# rs485.net
KiCad netlist of a schematic drawn in Altium Designer
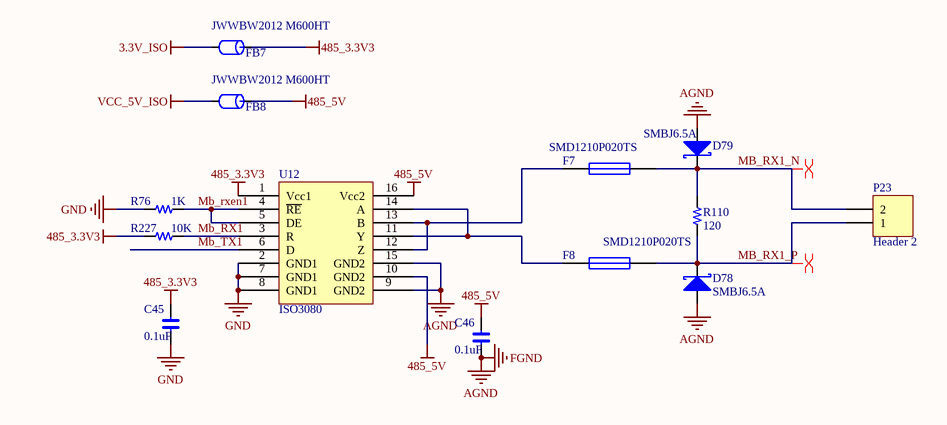
[diagram p0: rs485.SchDoc]

(export (version "E")
  (design (tool "Eeschema 10.0.6"))
  (components
    (comp (ref "C45")
      (value "0.1uF")
      (footprint "0603C")
      (description "C")
      (libsource (lib "Schlib_20110825") (part "C"))
    )
    (comp (ref "C46")
      (value "0.1uF")
      (footprint "0603C")
      (description "C")
      (libsource (lib "Schlib_20110825") (part "C"))
    )
    (comp (ref "D78")
      (value "SMBJ6.5A")
      (footprint "SMB")
      (description "Schottky Diode")
      (libsource (lib "*") (part "DIODE S"))
    )
    (comp (ref "D79")
      (value "SMBJ6.5A")
      (footprint "SMB")
      (description "Schottky Diode")
      (libsource (lib "*") (part "DIODE S"))
    )
    (comp (ref "F7")
      (value "SMD1210P020TS")
      (footprint "1206R")
      (description "Fuse")
      (fields (field (name "PUBLISHER") "Altium Limited"))
      (libsource (lib "Miscellaneous Devices") (part "Fuse 1"))
    )
    (comp (ref "F8")
      (value "SMD1210P020TS")
      (footprint "1206R")
      (description "Fuse")
      (fields (field (name "PUBLISHER") "Altium Limited"))
      (libsource (lib "Miscellaneous Devices") (part "Fuse 1"))
    )
    (comp (ref "FB7")
      (value "JWWBW2012 M600HT")
      (footprint "0805CZ")
      (libsource (lib "Schlib_20110825") (part "FB"))
    )
    (comp (ref "FB8")
      (value "JWWBW2012 M600HT")
      (footprint "0805CZ")
      (libsource (lib "Schlib_20110825") (part "FB"))
    )
    (comp (ref "P23")
      (value "Header 2")
      (footprint "2X2.54MMZ")
      (description "Header, 2-Pin")
      (fields (field (name "PUBLISHER") "Altium Limited"))
      (libsource (lib "Miscellaneous Connectors") (part "Header 2"))
    )
    (comp (ref "R76") (value "1K") (footprint "0603R") (description "R") (libsource (lib "JRJ_1") (part "R")))
    (comp (ref "R110")
      (value "120")
      (footprint "0603R")
      (description "R")
      (libsource (lib "JRJ_1") (part "R"))
    )
    (comp (ref "R227")
      (value "10K")
      (footprint "0603R")
      (description "R")
      (libsource (lib "JRJ_1") (part "R"))
    )
    (comp (ref "U12") (value "ISO3080") (footprint "SO-16") (libsource (lib "Schlib1") (part "ISO3080")))
  )
  (nets
    (net (code "1") (name "/MB_RX1_N") (class "Default")
      (node (ref "D79") (pin "2") (pinfunction "K_2") (pintype "passive"))
      (node (ref "F7") (pin "2") (pinfunction "2_2") (pintype "passive"))
      (node (ref "P23") (pin "2") (pinfunction "2_2") (pintype "passive"))
      (node (ref "R110") (pin "1") (pintype "passive"))
    )
    (net (code "2") (name "/MB_RX1_P") (class "Default")
      (node (ref "D78") (pin "2") (pinfunction "K_2") (pintype "passive"))
      (node (ref "F8") (pin "2") (pinfunction "2_2") (pintype "passive"))
      (node (ref "P23") (pin "1") (pinfunction "1_1") (pintype "passive"))
      (node (ref "R110") (pin "2") (pintype "passive"))
    )
    (net (code "3") (name "/Mb_RX1") (class "Default")
      (node (ref "R227") (pin "1") (pintype "passive"))
      (node (ref "U12") (pin "3") (pinfunction "R_3") (pintype "passive"))
    )
    (net (code "4") (name "/Mb_TX1") (class "Default")
      (node (ref "U12") (pin "6") (pinfunction "D_6") (pintype "passive"))
    )
    (net (code "5") (name "/Mb_rxen1") (class "Default")
      (node (ref "R76") (pin "1") (pintype "passive"))
      (node (ref "U12") (pin "4") (pinfunction "~{RE}_4") (pintype "passive"))
      (node (ref "U12") (pin "5") (pinfunction "DE_5") (pintype "passive"))
    )
    (net (code "6") (name "3.3V_ISO") (class "Default") (node (ref "FB7") (pin "2") (pintype "passive")))
    (net (code "7") (name "485_3.3V3") (class "Default")
      (node (ref "C45") (pin "2") (pintype "passive"))
      (node (ref "FB7") (pin "1") (pintype "passive"))
      (node (ref "R227") (pin "2") (pintype "passive"))
      (node (ref "U12") (pin "1") (pinfunction "Vcc1_1") (pintype "passive"))
    )
    (net (code "8") (name "485_5V") (class "Default")
      (node (ref "C46") (pin "2") (pintype "passive"))
      (node (ref "FB8") (pin "1") (pintype "passive"))
      (node (ref "U12") (pin "10") (pinfunction "GND2_10") (pintype "passive"))
      (node (ref "U12") (pin "16") (pinfunction "Vcc2_16") (pintype "passive"))
    )
    (net (code "9") (name "AGND") (class "Default")
      (node (ref "C46") (pin "1") (pintype "passive"))
      (node (ref "D78") (pin "1") (pinfunction "A_1") (pintype "passive"))
      (node (ref "D79") (pin "1") (pinfunction "A_1") (pintype "passive"))
      (node (ref "U12") (pin "15") (pinfunction "GND2_15") (pintype "passive"))
      (node (ref "U12") (pin "9") (pinfunction "GND2_9") (pintype "passive"))
    )
    (net (code "10") (name "GND") (class "Default")
      (node (ref "C45") (pin "1") (pintype "passive"))
      (node (ref "R76") (pin "2") (pintype "passive"))
      (node (ref "U12") (pin "2") (pinfunction "GND1_2") (pintype "passive"))
      (node (ref "U12") (pin "7") (pinfunction "GND1_7") (pintype "passive"))
      (node (ref "U12") (pin "8") (pinfunction "GND1_8") (pintype "passive"))
    )
    (net (code "11") (name "Net-(U12-A)") (class "Default")
      (node (ref "F8") (pin "1") (pinfunction "1_1") (pintype "passive"))
      (node (ref "U12") (pin "11") (pinfunction "Y_11") (pintype "passive"))
      (node (ref "U12") (pin "14") (pinfunction "A_14") (pintype "passive"))
    )
    (net (code "12") (name "Net-(U12-B)") (class "Default")
      (node (ref "F7") (pin "1") (pinfunction "1_1") (pintype "passive"))
      (node (ref "U12") (pin "12") (pinfunction "Z_12") (pintype "passive"))
      (node (ref "U12") (pin "13") (pinfunction "B_13") (pintype "passive"))
    )
    (net (code "13") (name "VCC_5V_ISO") (class "Default") (node (ref "FB8") (pin "2") (pintype "passive")))
  )
)
